# DS3231_Shield.net
KiCad netlist of a schematic drawn in EAGLE
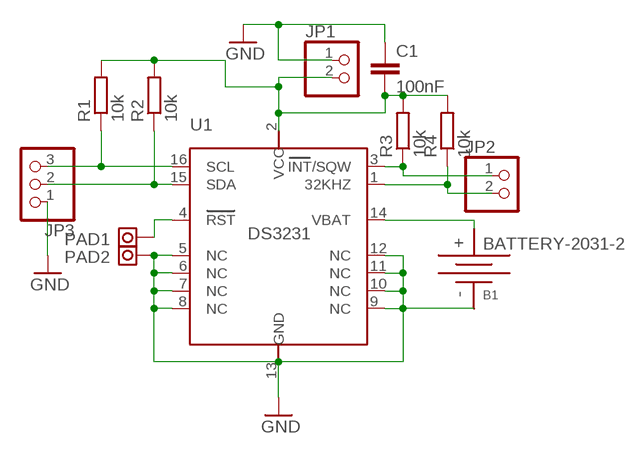
[diagram p0: schematic, sheet 1]

(export (version "E")
  (design (tool "Eeschema 10.0.6"))
  (components
    (comp (ref "B1")
      (value "BATTERY-2031-2")
      (footprint "eagle-import:BTH2032-2")
      (libsource (lib "eagle-import") (part "BATTERY-2031-2"))
    )
    (comp (ref "C1")
      (value "100nF")
      (footprint "eagle-import:C0805")
      (libsource (lib "eagle-import") (part "C-EUC0805"))
    )
    (comp (ref "JP1")
      (value "PINHD-1X2")
      (footprint "eagle-import:1X02")
      (libsource (lib "eagle-import") (part "PINHD-1X2"))
    )
    (comp (ref "JP2")
      (value "PINHD-1X2")
      (footprint "eagle-import:1X02")
      (libsource (lib "eagle-import") (part "PINHD-1X2"))
    )
    (comp (ref "JP3")
      (value "PINHD-1X3")
      (footprint "eagle-import:1X03")
      (libsource (lib "eagle-import") (part "PINHD-1X3"))
    )
    (comp (ref "PAD1")
      (value "PAD")
      (footprint "eagle-import:PAD")
      (libsource (lib "eagle-import") (part "PAD"))
    )
    (comp (ref "PAD2")
      (value "PAD")
      (footprint "eagle-import:PAD")
      (libsource (lib "eagle-import") (part "PAD"))
    )
    (comp (ref "R1")
      (value "10k")
      (footprint "eagle-import:R0805")
      (libsource (lib "eagle-import") (part "R-EU_R0805"))
    )
    (comp (ref "R2")
      (value "10k")
      (footprint "eagle-import:R0805")
      (libsource (lib "eagle-import") (part "R-EU_R0805"))
    )
    (comp (ref "R3")
      (value "10k")
      (footprint "eagle-import:R0805")
      (libsource (lib "eagle-import") (part "R-EU_R0805"))
    )
    (comp (ref "R4")
      (value "10k")
      (footprint "eagle-import:R0805")
      (libsource (lib "eagle-import") (part "R-EU_R0805"))
    )
    (comp (ref "U1")
      (value "DS3231")
      (footprint "eagle-import:SO16L")
      (libsource (lib "eagle-import") (part "DS3231"))
    )
  )
  (nets
    (net (code "1") (name "GND") (class "Default")
      (node (ref "B1") (pin "-") (pinfunction "-_-") (pintype "power_in"))
      (node (ref "C1") (pin "1") (pinfunction "1_1") (pintype "passive"))
      (node (ref "JP1") (pin "1") (pinfunction "1_1") (pintype "passive"))
      (node (ref "JP3") (pin "1") (pinfunction "1_1") (pintype "passive"))
      (node (ref "PAD2") (pin "P$1") (pinfunction "PAD_P$1") (pintype "bidirectional"))
      (node (ref "U1") (pin "10") (pinfunction "NC_10") (pintype "bidirectional"))
      (node (ref "U1") (pin "11") (pinfunction "NC_11") (pintype "bidirectional"))
      (node (ref "U1") (pin "12") (pinfunction "NC_12") (pintype "bidirectional"))
      (node (ref "U1") (pin "13") (pinfunction "GND_13") (pintype "power_in"))
      (node (ref "U1") (pin "5") (pinfunction "NC_5") (pintype "bidirectional"))
      (node (ref "U1") (pin "6") (pinfunction "NC_6") (pintype "bidirectional"))
      (node (ref "U1") (pin "7") (pinfunction "NC_7") (pintype "bidirectional"))
      (node (ref "U1") (pin "8") (pinfunction "NC_8") (pintype "bidirectional"))
      (node (ref "U1") (pin "9") (pinfunction "NC_9") (pintype "bidirectional"))
    )
    (net (code "2") (name "Net-(PAD1-PAD)") (class "Default")
      (node (ref "PAD1") (pin "P$1") (pinfunction "PAD_P$1") (pintype "bidirectional"))
      (node (ref "U1") (pin "4") (pinfunction "RST_4") (pintype "bidirectional"))
    )
    (net (code "3") (name "Net-(U1-32KHZ)") (class "Default")
      (node (ref "JP2") (pin "2") (pinfunction "2_2") (pintype "passive"))
      (node (ref "R4") (pin "1") (pinfunction "1_1") (pintype "passive"))
      (node (ref "U1") (pin "1") (pinfunction "32KHZ_1") (pintype "bidirectional"))
    )
    (net (code "4") (name "Net-(U1-INT{slash}SQW)") (class "Default")
      (node (ref "JP2") (pin "1") (pinfunction "1_1") (pintype "passive"))
      (node (ref "R3") (pin "1") (pinfunction "1_1") (pintype "passive"))
      (node (ref "U1") (pin "3") (pinfunction "INT/SQW_3") (pintype "bidirectional"))
    )
    (net (code "5") (name "Net-(U1-SCL)") (class "Default")
      (node (ref "JP3") (pin "3") (pinfunction "3_3") (pintype "passive"))
      (node (ref "R1") (pin "1") (pinfunction "1_1") (pintype "passive"))
      (node (ref "U1") (pin "16") (pinfunction "SCL_16") (pintype "bidirectional"))
    )
    (net (code "6") (name "Net-(U1-SDA)") (class "Default")
      (node (ref "JP3") (pin "2") (pinfunction "2_2") (pintype "passive"))
      (node (ref "R2") (pin "1") (pinfunction "1_1") (pintype "passive"))
      (node (ref "U1") (pin "15") (pinfunction "SDA_15") (pintype "bidirectional"))
    )
    (net (code "7") (name "Net-(U1-VBAT)") (class "Default")
      (node (ref "B1") (pin "+") (pinfunction "+_+") (pintype "power_in"))
      (node (ref "U1") (pin "14") (pinfunction "VBAT_14") (pintype "bidirectional"))
    )
    (net (code "8") (name "Net-(U1-VCC)") (class "Default")
      (node (ref "C1") (pin "2") (pinfunction "2_2") (pintype "passive"))
      (node (ref "JP1") (pin "2") (pinfunction "2_2") (pintype "passive"))
      (node (ref "R1") (pin "2") (pinfunction "2_2") (pintype "passive"))
      (node (ref "R2") (pin "2") (pinfunction "2_2") (pintype "passive"))
      (node (ref "R3") (pin "2") (pinfunction "2_2") (pintype "passive"))
      (node (ref "R4") (pin "2") (pinfunction "2_2") (pintype "passive"))
      (node (ref "U1") (pin "2") (pinfunction "VCC_2") (pintype "power_in"))
    )
  )
)
